# Adafruit_OLED_128x32_Mono.net
KiCad netlist of a schematic drawn in EAGLE
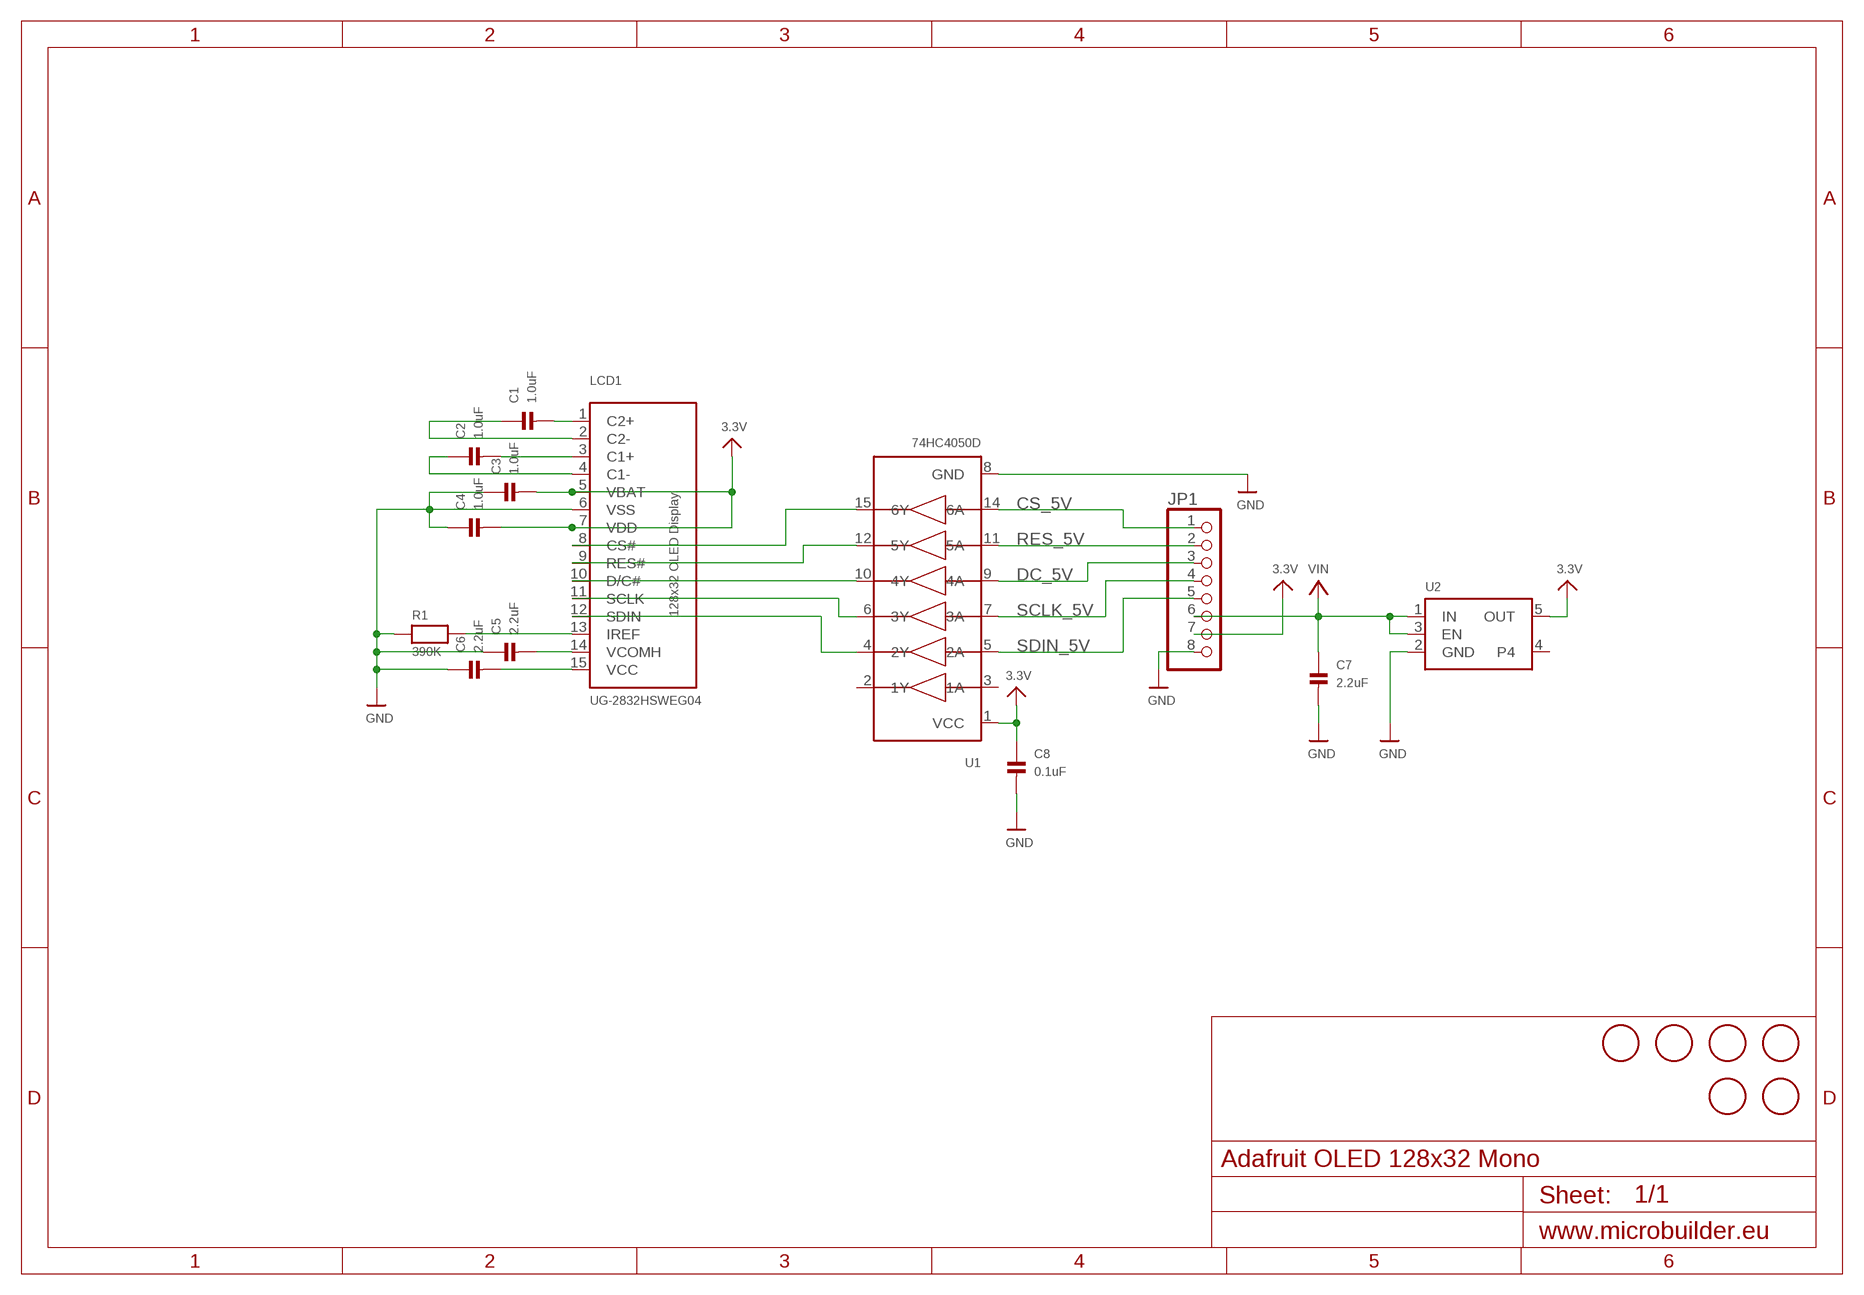
[diagram p0: schematic, sheet 1]

(export (version "E")
  (design (tool "Eeschema 10.0.6"))
  (components
    (comp (ref "C1")
      (value "1.0uF")
      (footprint "eagle-import:0805")
      (libsource (lib "eagle-import") (part "CAP_CERAMIC0805"))
    )
    (comp (ref "C2")
      (value "1.0uF")
      (footprint "eagle-import:0805")
      (libsource (lib "eagle-import") (part "CAP_CERAMIC0805"))
    )
    (comp (ref "C3")
      (value "1.0uF")
      (footprint "eagle-import:0805")
      (libsource (lib "eagle-import") (part "CAP_CERAMIC0805"))
    )
    (comp (ref "C4")
      (value "1.0uF")
      (footprint "eagle-import:0805")
      (libsource (lib "eagle-import") (part "CAP_CERAMIC0805"))
    )
    (comp (ref "C5")
      (value "2.2uF")
      (footprint "eagle-import:0805")
      (libsource (lib "eagle-import") (part "CAP_CERAMIC0805"))
    )
    (comp (ref "C6")
      (value "2.2uF")
      (footprint "eagle-import:0805")
      (libsource (lib "eagle-import") (part "CAP_CERAMIC0805"))
    )
    (comp (ref "C7")
      (value "2.2uF")
      (footprint "eagle-import:0805")
      (libsource (lib "eagle-import") (part "CAP_CERAMIC0805"))
    )
    (comp (ref "C8")
      (value "0.1uF")
      (footprint "eagle-import:0805")
      (libsource (lib "eagle-import") (part "CAP_CERAMIC0805"))
    )
    (comp (ref "JP1")
      (value "HEADER-1X876MIL")
      (footprint "eagle-import:1X08_ROUND_76")
      (libsource (lib "eagle-import") (part "HEADER-1X876MIL"))
    )
    (comp (ref "LCD1")
      (value "UG-2832HSWEG04")
      (footprint "eagle-import:UG-2832HSWEG04_WRAPAROUND")
      (libsource (lib "eagle-import") (part "OLED_UG-2832HSWEG04WRAPAROUND"))
    )
    (comp (ref "R1")
      (value "390K")
      (footprint "eagle-import:0805")
      (libsource (lib "eagle-import") (part "RESISTOR0805"))
    )
    (comp (ref "U$2")
      (value "MOUNTINGHOLE2.0")
      (footprint "eagle-import:MOUNTINGHOLE_2.0_PLATED")
      (libsource (lib "eagle-import") (part "MOUNTINGHOLE2.0"))
    )
    (comp (ref "U$3")
      (value "MOUNTINGHOLE2.0")
      (footprint "eagle-import:MOUNTINGHOLE_2.0_PLATED")
      (libsource (lib "eagle-import") (part "MOUNTINGHOLE2.0"))
    )
    (comp (ref "U$4")
      (value "MOUNTINGHOLE2.0")
      (footprint "eagle-import:MOUNTINGHOLE_2.0_PLATED")
      (libsource (lib "eagle-import") (part "MOUNTINGHOLE2.0"))
    )
    (comp (ref "U$5")
      (value "MOUNTINGHOLE2.0")
      (footprint "eagle-import:MOUNTINGHOLE_2.0_PLATED")
      (libsource (lib "eagle-import") (part "MOUNTINGHOLE2.0"))
    )
    (comp (ref "U$6")
      (value "FIDUCIAL")
      (footprint "eagle-import:FIDUCIAL_1MM")
      (libsource (lib "eagle-import") (part "FIDUCIAL"))
    )
    (comp (ref "U$7")
      (value "FIDUCIAL")
      (footprint "eagle-import:FIDUCIAL_1MM")
      (libsource (lib "eagle-import") (part "FIDUCIAL"))
    )
    (comp (ref "U1")
      (value "74HC4050D")
      (footprint "eagle-import:SOIC16")
      (libsource (lib "eagle-import") (part "74HC4050D"))
    )
    (comp (ref "U2")
      (value "VREG_SOT23-5")
      (footprint "eagle-import:SOT23-5")
      (libsource (lib "eagle-import") (part "VREG_SOT23-5"))
    )
  )
  (nets
    (net (code "1") (name "/CS_5V") (class "Default")
      (node (ref "JP1") (pin "1") (pinfunction "1_1") (pintype "passive"))
      (node (ref "U1") (pin "14") (pinfunction "6A_14") (pintype "bidirectional"))
    )
    (net (code "2") (name "/DC_5V") (class "Default")
      (node (ref "JP1") (pin "3") (pinfunction "3_3") (pintype "passive"))
      (node (ref "U1") (pin "9") (pinfunction "4A_9") (pintype "bidirectional"))
    )
    (net (code "3") (name "/RES_5V") (class "Default")
      (node (ref "JP1") (pin "2") (pinfunction "2_2") (pintype "passive"))
      (node (ref "U1") (pin "11") (pinfunction "5A_11") (pintype "bidirectional"))
    )
    (net (code "4") (name "/SCLK_5V") (class "Default")
      (node (ref "JP1") (pin "4") (pinfunction "4_4") (pintype "passive"))
      (node (ref "U1") (pin "7") (pinfunction "3A_7") (pintype "bidirectional"))
    )
    (net (code "5") (name "/SDIN_5V") (class "Default")
      (node (ref "JP1") (pin "5") (pinfunction "5_5") (pintype "passive"))
      (node (ref "U1") (pin "5") (pinfunction "2A_5") (pintype "bidirectional"))
    )
    (net (code "6") (name "3.3V") (class "Default")
      (node (ref "C3") (pin "2") (pinfunction "P$2_2") (pintype "passive"))
      (node (ref "C4") (pin "2") (pinfunction "P$2_2") (pintype "passive"))
      (node (ref "C8") (pin "1") (pinfunction "P$1_1") (pintype "passive"))
      (node (ref "JP1") (pin "7") (pinfunction "7_7") (pintype "passive"))
      (node (ref "LCD1") (pin "5") (pinfunction "VBAT_5") (pintype "bidirectional"))
      (node (ref "LCD1") (pin "7") (pinfunction "VDD_7") (pintype "bidirectional"))
      (node (ref "U1") (pin "1") (pinfunction "VCC_1") (pintype "bidirectional"))
      (node (ref "U2") (pin "5") (pinfunction "OUT_5") (pintype "bidirectional"))
    )
    (net (code "7") (name "GND") (class "Default")
      (node (ref "C3") (pin "1") (pinfunction "P$1_1") (pintype "passive"))
      (node (ref "C4") (pin "1") (pinfunction "P$1_1") (pintype "passive"))
      (node (ref "C5") (pin "1") (pinfunction "P$1_1") (pintype "passive"))
      (node (ref "C6") (pin "1") (pinfunction "P$1_1") (pintype "passive"))
      (node (ref "C7") (pin "2") (pinfunction "P$2_2") (pintype "passive"))
      (node (ref "C8") (pin "2") (pinfunction "P$2_2") (pintype "passive"))
      (node (ref "JP1") (pin "8") (pinfunction "8_8") (pintype "passive"))
      (node (ref "LCD1") (pin "6") (pinfunction "VSS_6") (pintype "bidirectional"))
      (node (ref "R1") (pin "1") (pinfunction "1_1") (pintype "passive"))
      (node (ref "U1") (pin "8") (pinfunction "GND_8") (pintype "bidirectional"))
      (node (ref "U2") (pin "2") (pinfunction "GND_2") (pintype "bidirectional"))
    )
    (net (code "8") (name "Net-(C1-P$1)") (class "Default")
      (node (ref "C1") (pin "1") (pinfunction "P$1_1") (pintype "passive"))
      (node (ref "LCD1") (pin "2") (pinfunction "C2-_2") (pintype "bidirectional"))
    )
    (net (code "9") (name "Net-(C1-P$2)") (class "Default")
      (node (ref "C1") (pin "2") (pinfunction "P$2_2") (pintype "passive"))
      (node (ref "LCD1") (pin "1") (pinfunction "C2+_1") (pintype "bidirectional"))
    )
    (net (code "10") (name "Net-(C2-P$1)") (class "Default")
      (node (ref "C2") (pin "1") (pinfunction "P$1_1") (pintype "passive"))
      (node (ref "LCD1") (pin "4") (pinfunction "C1-_4") (pintype "bidirectional"))
    )
    (net (code "11") (name "Net-(C2-P$2)") (class "Default")
      (node (ref "C2") (pin "2") (pinfunction "P$2_2") (pintype "passive"))
      (node (ref "LCD1") (pin "3") (pinfunction "C1+_3") (pintype "bidirectional"))
    )
    (net (code "12") (name "Net-(C5-P$2)") (class "Default")
      (node (ref "C5") (pin "2") (pinfunction "P$2_2") (pintype "passive"))
      (node (ref "LCD1") (pin "14") (pinfunction "VCOMH_14") (pintype "bidirectional"))
    )
    (net (code "13") (name "Net-(C6-P$2)") (class "Default")
      (node (ref "C6") (pin "2") (pinfunction "P$2_2") (pintype "passive"))
      (node (ref "LCD1") (pin "15") (pinfunction "VCC_15") (pintype "bidirectional"))
    )
    (net (code "14") (name "Net-(LCD1-CS#)") (class "Default")
      (node (ref "LCD1") (pin "8") (pinfunction "CS#_8") (pintype "bidirectional"))
      (node (ref "U1") (pin "15") (pinfunction "6Y_15") (pintype "bidirectional"))
    )
    (net (code "15") (name "Net-(LCD1-D{slash}C#)") (class "Default")
      (node (ref "LCD1") (pin "10") (pinfunction "D/C#_10") (pintype "bidirectional"))
      (node (ref "U1") (pin "10") (pinfunction "4Y_10") (pintype "bidirectional"))
    )
    (net (code "16") (name "Net-(LCD1-IREF)") (class "Default")
      (node (ref "LCD1") (pin "13") (pinfunction "IREF_13") (pintype "bidirectional"))
      (node (ref "R1") (pin "2") (pinfunction "2_2") (pintype "passive"))
    )
    (net (code "17") (name "Net-(LCD1-RES#)") (class "Default")
      (node (ref "LCD1") (pin "9") (pinfunction "RES#_9") (pintype "bidirectional"))
      (node (ref "U1") (pin "12") (pinfunction "5Y_12") (pintype "bidirectional"))
    )
    (net (code "18") (name "Net-(LCD1-SCLK)") (class "Default")
      (node (ref "LCD1") (pin "11") (pinfunction "SCLK_11") (pintype "bidirectional"))
      (node (ref "U1") (pin "6") (pinfunction "3Y_6") (pintype "bidirectional"))
    )
    (net (code "19") (name "Net-(LCD1-SDIN)") (class "Default")
      (node (ref "LCD1") (pin "12") (pinfunction "SDIN_12") (pintype "bidirectional"))
      (node (ref "U1") (pin "4") (pinfunction "2Y_4") (pintype "bidirectional"))
    )
    (net (code "20") (name "VIN") (class "Default")
      (node (ref "C7") (pin "1") (pinfunction "P$1_1") (pintype "passive"))
      (node (ref "JP1") (pin "6") (pinfunction "6_6") (pintype "passive"))
      (node (ref "U2") (pin "1") (pinfunction "IN_1") (pintype "bidirectional"))
      (node (ref "U2") (pin "3") (pinfunction "EN_3") (pintype "bidirectional"))
    )
    (net (code "21") (name "unconnected-(U1-1A-Pad3)") (class "Default")
      (node (ref "U1") (pin "3") (pinfunction "1A_3") (pintype "bidirectional"))
    )
    (net (code "22") (name "unconnected-(U1-1Y-Pad2)") (class "Default")
      (node (ref "U1") (pin "2") (pinfunction "1Y_2") (pintype "bidirectional"))
    )
    (net (code "23") (name "unconnected-(U2-P4-Pad4)") (class "Default")
      (node (ref "U2") (pin "4") (pinfunction "P4_4") (pintype "bidirectional"))
    )
  )
)
